# uart_optoizolation.net
KiCad netlist of a schematic drawn in Altium Designer
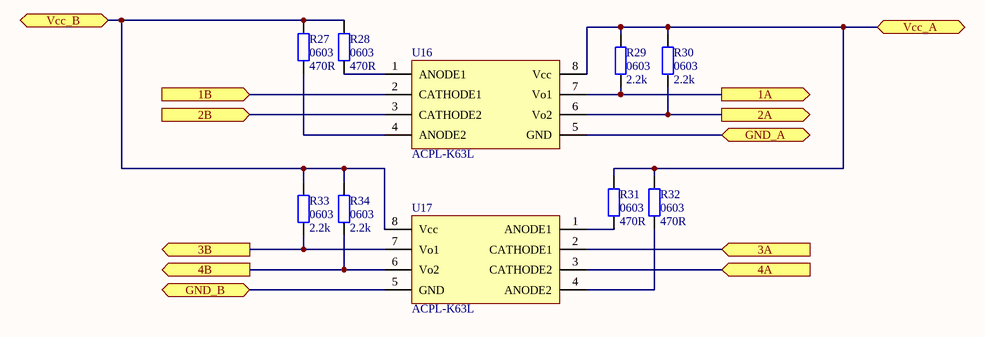
[diagram p0: uart_optoizolation.SchDoc]

(export (version "E")
  (design (tool "Eeschema 10.0.6"))
  (components
    (comp (ref "R27")
      (value "0603")
      (footprint "SMD_Resistor_0603")
      (description "Resistor")
      (fields (field (name "ALTIUM_VALUE") "470R") (field (name "PUBLISHER") "Altium Limited"))
      (libsource (lib "Miscellaneous Devices") (part "Res2"))
    )
    (comp (ref "R28")
      (value "0603")
      (footprint "SMD_Resistor_0603")
      (description "Resistor")
      (fields (field (name "ALTIUM_VALUE") "470R") (field (name "PUBLISHER") "Altium Limited"))
      (libsource (lib "Miscellaneous Devices") (part "Res2"))
    )
    (comp (ref "R29")
      (value "0603")
      (footprint "SMD_Resistor_0603")
      (description "Resistor")
      (fields (field (name "ALTIUM_VALUE") "2.2k") (field (name "PUBLISHER") "Altium Limited"))
      (libsource (lib "Miscellaneous Devices") (part "Res2"))
    )
    (comp (ref "R30")
      (value "0603")
      (footprint "SMD_Resistor_0603")
      (description "Resistor")
      (fields (field (name "ALTIUM_VALUE") "2.2k") (field (name "PUBLISHER") "Altium Limited"))
      (libsource (lib "Miscellaneous Devices") (part "Res2"))
    )
    (comp (ref "R31")
      (value "0603")
      (footprint "SMD_Resistor_0603")
      (description "Resistor")
      (fields (field (name "ALTIUM_VALUE") "470R") (field (name "PUBLISHER") "Altium Limited"))
      (libsource (lib "Miscellaneous Devices") (part "Res2"))
    )
    (comp (ref "R32")
      (value "0603")
      (footprint "SMD_Resistor_0603")
      (description "Resistor")
      (fields (field (name "ALTIUM_VALUE") "470R") (field (name "PUBLISHER") "Altium Limited"))
      (libsource (lib "Miscellaneous Devices") (part "Res2"))
    )
    (comp (ref "R33")
      (value "0603")
      (footprint "SMD_Resistor_0603")
      (description "Resistor")
      (fields (field (name "ALTIUM_VALUE") "2.2k") (field (name "PUBLISHER") "Altium Limited"))
      (libsource (lib "Miscellaneous Devices") (part "Res2"))
    )
    (comp (ref "R34")
      (value "0603")
      (footprint "SMD_Resistor_0603")
      (description "Resistor")
      (fields (field (name "ALTIUM_VALUE") "2.2k") (field (name "PUBLISHER") "Altium Limited"))
      (libsource (lib "Miscellaneous Devices") (part "Res2"))
    )
    (comp (ref "U16")
      (value "ACPL-K63L")
      (footprint "SOIC-8_M")
      (description "High Speed LVTTL Compatible 3.3 Volt/5 Volt Optocouplers")
      (libsource (lib "") (part "ACPL-K63L_1"))
    )
    (comp (ref "U17")
      (value "ACPL-K63L")
      (footprint "SOIC-8_M")
      (description "High Speed LVTTL Compatible 3.3 Volt/5 Volt Optocouplers")
      (libsource (lib "GG") (part "ACPL-K63L"))
    )
  )
  (nets
    (net (code "1") (name "/1A") (class "Default")
      (node (ref "R29") (pin "1") (pinfunction "1_1") (pintype "passive"))
      (node (ref "U16") (pin "7") (pinfunction "Vo1_7") (pintype "power_in"))
    )
    (net (code "2") (name "/1B") (class "Default")
      (node (ref "U16") (pin "2") (pinfunction "CATHODE1_2") (pintype "power_in"))
    )
    (net (code "3") (name "/2A") (class "Default")
      (node (ref "R30") (pin "1") (pinfunction "1_1") (pintype "passive"))
      (node (ref "U16") (pin "6") (pinfunction "Vo2_6") (pintype "power_in"))
    )
    (net (code "4") (name "/2B") (class "Default")
      (node (ref "U16") (pin "3") (pinfunction "CATHODE2_3") (pintype "power_in"))
    )
    (net (code "5") (name "/3A") (class "Default")
      (node (ref "U17") (pin "2") (pinfunction "CATHODE1_2") (pintype "power_in"))
    )
    (net (code "6") (name "/3B") (class "Default")
      (node (ref "R33") (pin "1") (pinfunction "1_1") (pintype "passive"))
      (node (ref "U17") (pin "7") (pinfunction "Vo1_7") (pintype "power_in"))
    )
    (net (code "7") (name "/4A") (class "Default")
      (node (ref "U17") (pin "3") (pinfunction "CATHODE2_3") (pintype "power_in"))
    )
    (net (code "8") (name "/4B") (class "Default")
      (node (ref "R34") (pin "1") (pinfunction "1_1") (pintype "passive"))
      (node (ref "U17") (pin "6") (pinfunction "Vo2_6") (pintype "power_in"))
    )
    (net (code "9") (name "/GND_A") (class "Default")
      (node (ref "U16") (pin "5") (pinfunction "GND_5") (pintype "power_in"))
    )
    (net (code "10") (name "/GND_B") (class "Default")
      (node (ref "U17") (pin "5") (pinfunction "GND_5") (pintype "power_in"))
    )
    (net (code "11") (name "/Vcc_A") (class "Default")
      (node (ref "R29") (pin "2") (pinfunction "2_2") (pintype "passive"))
      (node (ref "R30") (pin "2") (pinfunction "2_2") (pintype "passive"))
      (node (ref "R31") (pin "2") (pinfunction "2_2") (pintype "passive"))
      (node (ref "R32") (pin "2") (pinfunction "2_2") (pintype "passive"))
      (node (ref "U16") (pin "8") (pinfunction "Vcc_8") (pintype "power_in"))
    )
    (net (code "12") (name "/Vcc_B") (class "Default")
      (node (ref "R27") (pin "2") (pinfunction "2_2") (pintype "passive"))
      (node (ref "R28") (pin "2") (pinfunction "2_2") (pintype "passive"))
      (node (ref "R33") (pin "2") (pinfunction "2_2") (pintype "passive"))
      (node (ref "R34") (pin "2") (pinfunction "2_2") (pintype "passive"))
      (node (ref "U17") (pin "8") (pinfunction "Vcc_8") (pintype "power_in"))
    )
    (net (code "13") (name "Net-(U16-ANODE1)") (class "Default")
      (node (ref "R28") (pin "1") (pinfunction "1_1") (pintype "passive"))
      (node (ref "U16") (pin "1") (pinfunction "ANODE1_1") (pintype "power_in"))
    )
    (net (code "14") (name "Net-(U16-ANODE2)") (class "Default")
      (node (ref "R27") (pin "1") (pinfunction "1_1") (pintype "passive"))
      (node (ref "U16") (pin "4") (pinfunction "ANODE2_4") (pintype "power_in"))
    )
    (net (code "15") (name "Net-(U17-ANODE1)") (class "Default")
      (node (ref "R31") (pin "1") (pinfunction "1_1") (pintype "passive"))
      (node (ref "U17") (pin "1") (pinfunction "ANODE1_1") (pintype "power_in"))
    )
    (net (code "16") (name "Net-(U17-ANODE2)") (class "Default")
      (node (ref "R32") (pin "1") (pinfunction "1_1") (pintype "passive"))
      (node (ref "U17") (pin "4") (pinfunction "ANODE2_4") (pintype "power_in"))
    )
  )
)
